# 51.net
KiCad netlist of a schematic drawn in Altium Designer
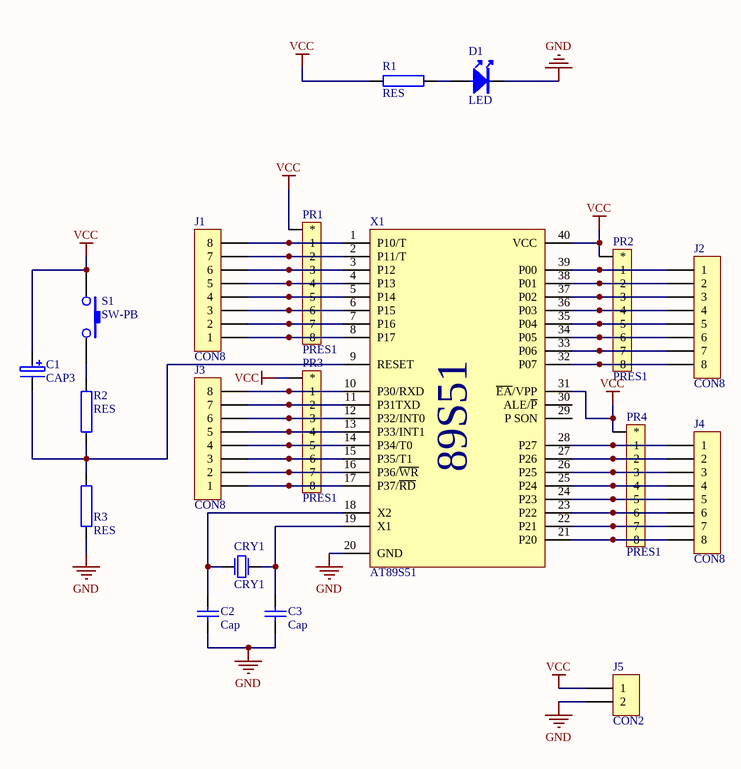
[diagram p0: 51最小系统.SchDoc]

(export (version "E")
  (design (tool "Eeschema 10.0.6"))
  (components
    (comp (ref "C1") (value "CAP3") (footprint "CAO1") (libsource (lib "C电容") (part "CAP3")))
    (comp (ref "C2")
      (value "Cap")
      (footprint "CAP2")
      (description "Capacitor")
      (fields (field (name "PUBLISHER") "Altium Limited"))
      (libsource (lib "Capacitance电容") (part "Cap"))
    )
    (comp (ref "C3")
      (value "Cap")
      (footprint "CAP2")
      (description "Capacitor")
      (fields (field (name "PUBLISHER") "Altium Limited"))
      (libsource (lib "Capacitance电容") (part "Cap"))
    )
    (comp (ref "CRY1")
      (value "CRY1")
      (footprint "JZ1")
      (description "6.0000 8.000  11.0592  12.0000 24.000")
      (libsource (lib "J晶振") (part "CRY1"))
    )
    (comp (ref "D1") (value "LED") (footprint "LED2") (libsource (lib "Diode二极管") (part "LED")))
    (comp (ref "J1")
      (value "CON8")
      (footprint "sip-8")
      (description "Connector")
      (libsource (lib "接口") (part "CON8"))
    )
    (comp (ref "J2")
      (value "CON8")
      (footprint "sip-8")
      (description "Connector")
      (libsource (lib "") (part "CON8_1"))
    )
    (comp (ref "J3")
      (value "CON8")
      (footprint "sip-8")
      (description "Connector")
      (libsource (lib "接口") (part "CON8"))
    )
    (comp (ref "J4")
      (value "CON8")
      (footprint "sip-8")
      (description "Connector")
      (libsource (lib "") (part "CON8_1"))
    )
    (comp (ref "J5")
      (value "CON2")
      (footprint "sip-2")
      (description "Connector")
      (libsource (lib "接口") (part "CON2"))
    )
    (comp (ref "PR1") (value "PRES1") (footprint "RP1") (libsource (lib "Resistance电阻") (part "PRES1")))
    (comp (ref "PR2") (value "PRES1") (footprint "RP1") (libsource (lib "Resistance电阻") (part "PRES1")))
    (comp (ref "PR3") (value "PRES1") (footprint "RP1") (libsource (lib "Resistance电阻") (part "PRES1")))
    (comp (ref "PR4") (value "PRES1") (footprint "RP1") (libsource (lib "Resistance电阻") (part "PRES1")))
    (comp (ref "R1") (value "RES") (footprint "AXIAL0.3") (libsource (lib "R电阻") (part "RES")))
    (comp (ref "R2") (value "RES") (footprint "AXIAL0.3") (libsource (lib "R电阻") (part "RES")))
    (comp (ref "R3") (value "RES") (footprint "AXIAL0.3") (libsource (lib "R电阻") (part "RES")))
    (comp (ref "S1") (value "SW-PB") (footprint "SW6*6") (libsource (lib "Switch开关") (part "SW-PB")))
    (comp (ref "X1") (value "AT89S51") (footprint "DIP-40") (libsource (lib "MCU") (part "AT89S51")))
  )
  (nets
    (net (code "1") (name "GND") (class "Default")
      (node (ref "C2") (pin "1") (pinfunction "1_1") (pintype "passive"))
      (node (ref "C3") (pin "1") (pinfunction "1_1") (pintype "passive"))
      (node (ref "D1") (pin "2") (pinfunction "2_2") (pintype "passive"))
      (node (ref "J5") (pin "2") (pinfunction "2_2") (pintype "passive"))
      (node (ref "R3") (pin "1") (pinfunction "1_1") (pintype "passive"))
      (node (ref "X1") (pin "20") (pinfunction "GND_20") (pintype "passive"))
    )
    (net (code "2") (name "Net-(CRY1-P1)") (class "Default")
      (node (ref "C2") (pin "2") (pinfunction "2_2") (pintype "passive"))
      (node (ref "CRY1") (pin "1") (pinfunction "P1_1") (pintype "passive"))
      (node (ref "X1") (pin "18") (pinfunction "X2_18") (pintype "passive"))
    )
    (net (code "3") (name "Net-(CRY1-P2)") (class "Default")
      (node (ref "C3") (pin "2") (pinfunction "2_2") (pintype "passive"))
      (node (ref "CRY1") (pin "2") (pinfunction "P2_2") (pintype "passive"))
      (node (ref "X1") (pin "19") (pinfunction "X1_19") (pintype "passive"))
    )
    (net (code "4") (name "Net-(D1-Pad1)") (class "Default")
      (node (ref "D1") (pin "1") (pinfunction "1_1") (pintype "passive"))
      (node (ref "R1") (pin "2") (pinfunction "2_2") (pintype "passive"))
    )
    (net (code "5") (name "Net-(PR1-1)") (class "Default")
      (node (ref "J1") (pin "8") (pinfunction "8_8") (pintype "passive"))
      (node (ref "PR1") (pin "2") (pinfunction "1_2") (pintype "passive"))
      (node (ref "X1") (pin "1") (pinfunction "P10/T_1") (pintype "passive"))
    )
    (net (code "6") (name "Net-(PR1-2)") (class "Default")
      (node (ref "J1") (pin "7") (pinfunction "7_7") (pintype "passive"))
      (node (ref "PR1") (pin "3") (pinfunction "2_3") (pintype "passive"))
      (node (ref "X1") (pin "2") (pinfunction "P11/T_2") (pintype "passive"))
    )
    (net (code "7") (name "Net-(PR1-3)") (class "Default")
      (node (ref "J1") (pin "6") (pinfunction "6_6") (pintype "passive"))
      (node (ref "PR1") (pin "4") (pinfunction "3_4") (pintype "passive"))
      (node (ref "X1") (pin "3") (pinfunction "P12_3") (pintype "passive"))
    )
    (net (code "8") (name "Net-(PR1-4)") (class "Default")
      (node (ref "J1") (pin "5") (pinfunction "5_5") (pintype "passive"))
      (node (ref "PR1") (pin "5") (pinfunction "4_5") (pintype "passive"))
      (node (ref "X1") (pin "4") (pinfunction "P13_4") (pintype "passive"))
    )
    (net (code "9") (name "Net-(PR1-5)") (class "Default")
      (node (ref "J1") (pin "4") (pinfunction "4_4") (pintype "passive"))
      (node (ref "PR1") (pin "6") (pinfunction "5_6") (pintype "passive"))
      (node (ref "X1") (pin "5") (pinfunction "P14_5") (pintype "passive"))
    )
    (net (code "10") (name "Net-(PR1-6)") (class "Default")
      (node (ref "J1") (pin "3") (pinfunction "3_3") (pintype "passive"))
      (node (ref "PR1") (pin "7") (pinfunction "6_7") (pintype "passive"))
      (node (ref "X1") (pin "6") (pinfunction "P15_6") (pintype "passive"))
    )
    (net (code "11") (name "Net-(PR1-7)") (class "Default")
      (node (ref "J1") (pin "2") (pinfunction "2_2") (pintype "passive"))
      (node (ref "PR1") (pin "8") (pinfunction "7_8") (pintype "passive"))
      (node (ref "X1") (pin "7") (pinfunction "P16_7") (pintype "passive"))
    )
    (net (code "12") (name "Net-(PR1-8)") (class "Default")
      (node (ref "J1") (pin "1") (pinfunction "1_1") (pintype "passive"))
      (node (ref "PR1") (pin "9") (pinfunction "8_9") (pintype "passive"))
      (node (ref "X1") (pin "8") (pinfunction "P17_8") (pintype "passive"))
    )
    (net (code "13") (name "Net-(PR2-1)") (class "Default")
      (node (ref "J2") (pin "1") (pinfunction "1_1") (pintype "passive"))
      (node (ref "PR2") (pin "2") (pinfunction "1_2") (pintype "passive"))
      (node (ref "X1") (pin "39") (pinfunction "P00_39") (pintype "passive"))
    )
    (net (code "14") (name "Net-(PR2-2)") (class "Default")
      (node (ref "J2") (pin "2") (pinfunction "2_2") (pintype "passive"))
      (node (ref "PR2") (pin "3") (pinfunction "2_3") (pintype "passive"))
      (node (ref "X1") (pin "38") (pinfunction "P01_38") (pintype "passive"))
    )
    (net (code "15") (name "Net-(PR2-3)") (class "Default")
      (node (ref "J2") (pin "3") (pinfunction "3_3") (pintype "passive"))
      (node (ref "PR2") (pin "4") (pinfunction "3_4") (pintype "passive"))
      (node (ref "X1") (pin "37") (pinfunction "P02_37") (pintype "passive"))
    )
    (net (code "16") (name "Net-(PR2-4)") (class "Default")
      (node (ref "J2") (pin "4") (pinfunction "4_4") (pintype "passive"))
      (node (ref "PR2") (pin "5") (pinfunction "4_5") (pintype "passive"))
      (node (ref "X1") (pin "36") (pinfunction "P03_36") (pintype "passive"))
    )
    (net (code "17") (name "Net-(PR2-5)") (class "Default")
      (node (ref "J2") (pin "5") (pinfunction "5_5") (pintype "passive"))
      (node (ref "PR2") (pin "6") (pinfunction "5_6") (pintype "passive"))
      (node (ref "X1") (pin "35") (pinfunction "P04_35") (pintype "passive"))
    )
    (net (code "18") (name "Net-(PR2-6)") (class "Default")
      (node (ref "J2") (pin "6") (pinfunction "6_6") (pintype "passive"))
      (node (ref "PR2") (pin "7") (pinfunction "6_7") (pintype "passive"))
      (node (ref "X1") (pin "34") (pinfunction "P05_34") (pintype "passive"))
    )
    (net (code "19") (name "Net-(PR2-7)") (class "Default")
      (node (ref "J2") (pin "7") (pinfunction "7_7") (pintype "passive"))
      (node (ref "PR2") (pin "8") (pinfunction "7_8") (pintype "passive"))
      (node (ref "X1") (pin "33") (pinfunction "P06_33") (pintype "passive"))
    )
    (net (code "20") (name "Net-(PR2-8)") (class "Default")
      (node (ref "J2") (pin "8") (pinfunction "8_8") (pintype "passive"))
      (node (ref "PR2") (pin "9") (pinfunction "8_9") (pintype "passive"))
      (node (ref "X1") (pin "32") (pinfunction "P07_32") (pintype "passive"))
    )
    (net (code "21") (name "Net-(PR3-1)") (class "Default")
      (node (ref "J3") (pin "8") (pinfunction "8_8") (pintype "passive"))
      (node (ref "PR3") (pin "2") (pinfunction "1_2") (pintype "passive"))
      (node (ref "X1") (pin "10") (pinfunction "P30/RXD_10") (pintype "passive"))
    )
    (net (code "22") (name "Net-(PR3-2)") (class "Default")
      (node (ref "J3") (pin "7") (pinfunction "7_7") (pintype "passive"))
      (node (ref "PR3") (pin "3") (pinfunction "2_3") (pintype "passive"))
      (node (ref "X1") (pin "11") (pinfunction "P31TXD_11") (pintype "passive"))
    )
    (net (code "23") (name "Net-(PR3-3)") (class "Default")
      (node (ref "J3") (pin "6") (pinfunction "6_6") (pintype "passive"))
      (node (ref "PR3") (pin "4") (pinfunction "3_4") (pintype "passive"))
      (node (ref "X1") (pin "12") (pinfunction "P32/INT0_12") (pintype "passive"))
    )
    (net (code "24") (name "Net-(PR3-4)") (class "Default")
      (node (ref "J3") (pin "5") (pinfunction "5_5") (pintype "passive"))
      (node (ref "PR3") (pin "5") (pinfunction "4_5") (pintype "passive"))
      (node (ref "X1") (pin "13") (pinfunction "P33/INT1_13") (pintype "passive"))
    )
    (net (code "25") (name "Net-(PR3-5)") (class "Default")
      (node (ref "J3") (pin "4") (pinfunction "4_4") (pintype "passive"))
      (node (ref "PR3") (pin "6") (pinfunction "5_6") (pintype "passive"))
      (node (ref "X1") (pin "14") (pinfunction "P34/T0_14") (pintype "passive"))
    )
    (net (code "26") (name "Net-(PR3-6)") (class "Default")
      (node (ref "J3") (pin "3") (pinfunction "3_3") (pintype "passive"))
      (node (ref "PR3") (pin "7") (pinfunction "6_7") (pintype "passive"))
      (node (ref "X1") (pin "15") (pinfunction "P35/T1_15") (pintype "passive"))
    )
    (net (code "27") (name "Net-(PR3-7)") (class "Default")
      (node (ref "J3") (pin "2") (pinfunction "2_2") (pintype "passive"))
      (node (ref "PR3") (pin "8") (pinfunction "7_8") (pintype "passive"))
      (node (ref "X1") (pin "16") (pinfunction "P36/~{WR}_16") (pintype "passive"))
    )
    (net (code "28") (name "Net-(PR3-8)") (class "Default")
      (node (ref "J3") (pin "1") (pinfunction "1_1") (pintype "passive"))
      (node (ref "PR3") (pin "9") (pinfunction "8_9") (pintype "passive"))
      (node (ref "X1") (pin "17") (pinfunction "P37/~{RD}_17") (pintype "passive"))
    )
    (net (code "29") (name "Net-(PR4-1)") (class "Default")
      (node (ref "J4") (pin "1") (pinfunction "1_1") (pintype "passive"))
      (node (ref "PR4") (pin "2") (pinfunction "1_2") (pintype "passive"))
      (node (ref "X1") (pin "28") (pinfunction "P27_28") (pintype "passive"))
    )
    (net (code "30") (name "Net-(PR4-2)") (class "Default")
      (node (ref "J4") (pin "2") (pinfunction "2_2") (pintype "passive"))
      (node (ref "PR4") (pin "3") (pinfunction "2_3") (pintype "passive"))
      (node (ref "X1") (pin "27") (pinfunction "P26_27") (pintype "passive"))
    )
    (net (code "31") (name "Net-(PR4-3)") (class "Default")
      (node (ref "J4") (pin "3") (pinfunction "3_3") (pintype "passive"))
      (node (ref "PR4") (pin "4") (pinfunction "3_4") (pintype "passive"))
      (node (ref "X1") (pin "26") (pinfunction "P25_26") (pintype "passive"))
    )
    (net (code "32") (name "Net-(PR4-4)") (class "Default")
      (node (ref "J4") (pin "4") (pinfunction "4_4") (pintype "passive"))
      (node (ref "PR4") (pin "5") (pinfunction "4_5") (pintype "passive"))
      (node (ref "X1") (pin "25") (pinfunction "P24_25") (pintype "passive"))
    )
    (net (code "33") (name "Net-(PR4-5)") (class "Default")
      (node (ref "J4") (pin "5") (pinfunction "5_5") (pintype "passive"))
      (node (ref "PR4") (pin "6") (pinfunction "5_6") (pintype "passive"))
      (node (ref "X1") (pin "24") (pinfunction "P23_24") (pintype "passive"))
    )
    (net (code "34") (name "Net-(PR4-6)") (class "Default")
      (node (ref "J4") (pin "6") (pinfunction "6_6") (pintype "passive"))
      (node (ref "PR4") (pin "7") (pinfunction "6_7") (pintype "passive"))
      (node (ref "X1") (pin "23") (pinfunction "P22_23") (pintype "passive"))
    )
    (net (code "35") (name "Net-(PR4-7)") (class "Default")
      (node (ref "J4") (pin "7") (pinfunction "7_7") (pintype "passive"))
      (node (ref "PR4") (pin "8") (pinfunction "7_8") (pintype "passive"))
      (node (ref "X1") (pin "22") (pinfunction "P21_22") (pintype "passive"))
    )
    (net (code "36") (name "Net-(PR4-8)") (class "Default")
      (node (ref "J4") (pin "8") (pinfunction "8_8") (pintype "passive"))
      (node (ref "PR4") (pin "9") (pinfunction "8_9") (pintype "passive"))
      (node (ref "X1") (pin "21") (pinfunction "P20_21") (pintype "passive"))
    )
    (net (code "37") (name "Net-(R2-Pad2)") (class "Default")
      (node (ref "R2") (pin "2") (pinfunction "2_2") (pintype "passive"))
      (node (ref "S1") (pin "2") (pinfunction "2_2") (pintype "passive"))
    )
    (net (code "38") (name "Net-(X1-RESET)") (class "Default")
      (node (ref "C1") (pin "2") (pintype "passive"))
      (node (ref "R2") (pin "1") (pinfunction "1_1") (pintype "passive"))
      (node (ref "R3") (pin "2") (pinfunction "2_2") (pintype "passive"))
      (node (ref "X1") (pin "9") (pinfunction "RESET_9") (pintype "passive"))
    )
    (net (code "39") (name "VCC") (class "Default")
      (node (ref "C1") (pin "1") (pintype "passive"))
      (node (ref "J5") (pin "1") (pinfunction "1_1") (pintype "passive"))
      (node (ref "PR1") (pin "1") (pinfunction "*_1") (pintype "passive"))
      (node (ref "PR2") (pin "1") (pinfunction "*_1") (pintype "passive"))
      (node (ref "PR3") (pin "1") (pinfunction "*_1") (pintype "passive"))
      (node (ref "PR4") (pin "1") (pinfunction "*_1") (pintype "passive"))
      (node (ref "R1") (pin "1") (pinfunction "1_1") (pintype "passive"))
      (node (ref "S1") (pin "1") (pinfunction "1_1") (pintype "passive"))
      (node (ref "X1") (pin "31") (pinfunction "~{EA}/VPP_31") (pintype "passive"))
      (node (ref "X1") (pin "40") (pinfunction "VCC_40") (pintype "passive"))
    )
    (net (code "40") (name "unconnected-(X1-ALE{slash}~{P}-Pad30)") (class "Default")
      (node (ref "X1") (pin "30") (pinfunction "ALE/~{P}_30") (pintype "passive"))
    )
    (net (code "41") (name "unconnected-(X1-P_SON-Pad29)") (class "Default")
      (node (ref "X1") (pin "29") (pinfunction "P_SON_29") (pintype "passive"))
    )
  )
)
